# sch_light_rgb.net
KiCad netlist of a schematic drawn in EasyEDA
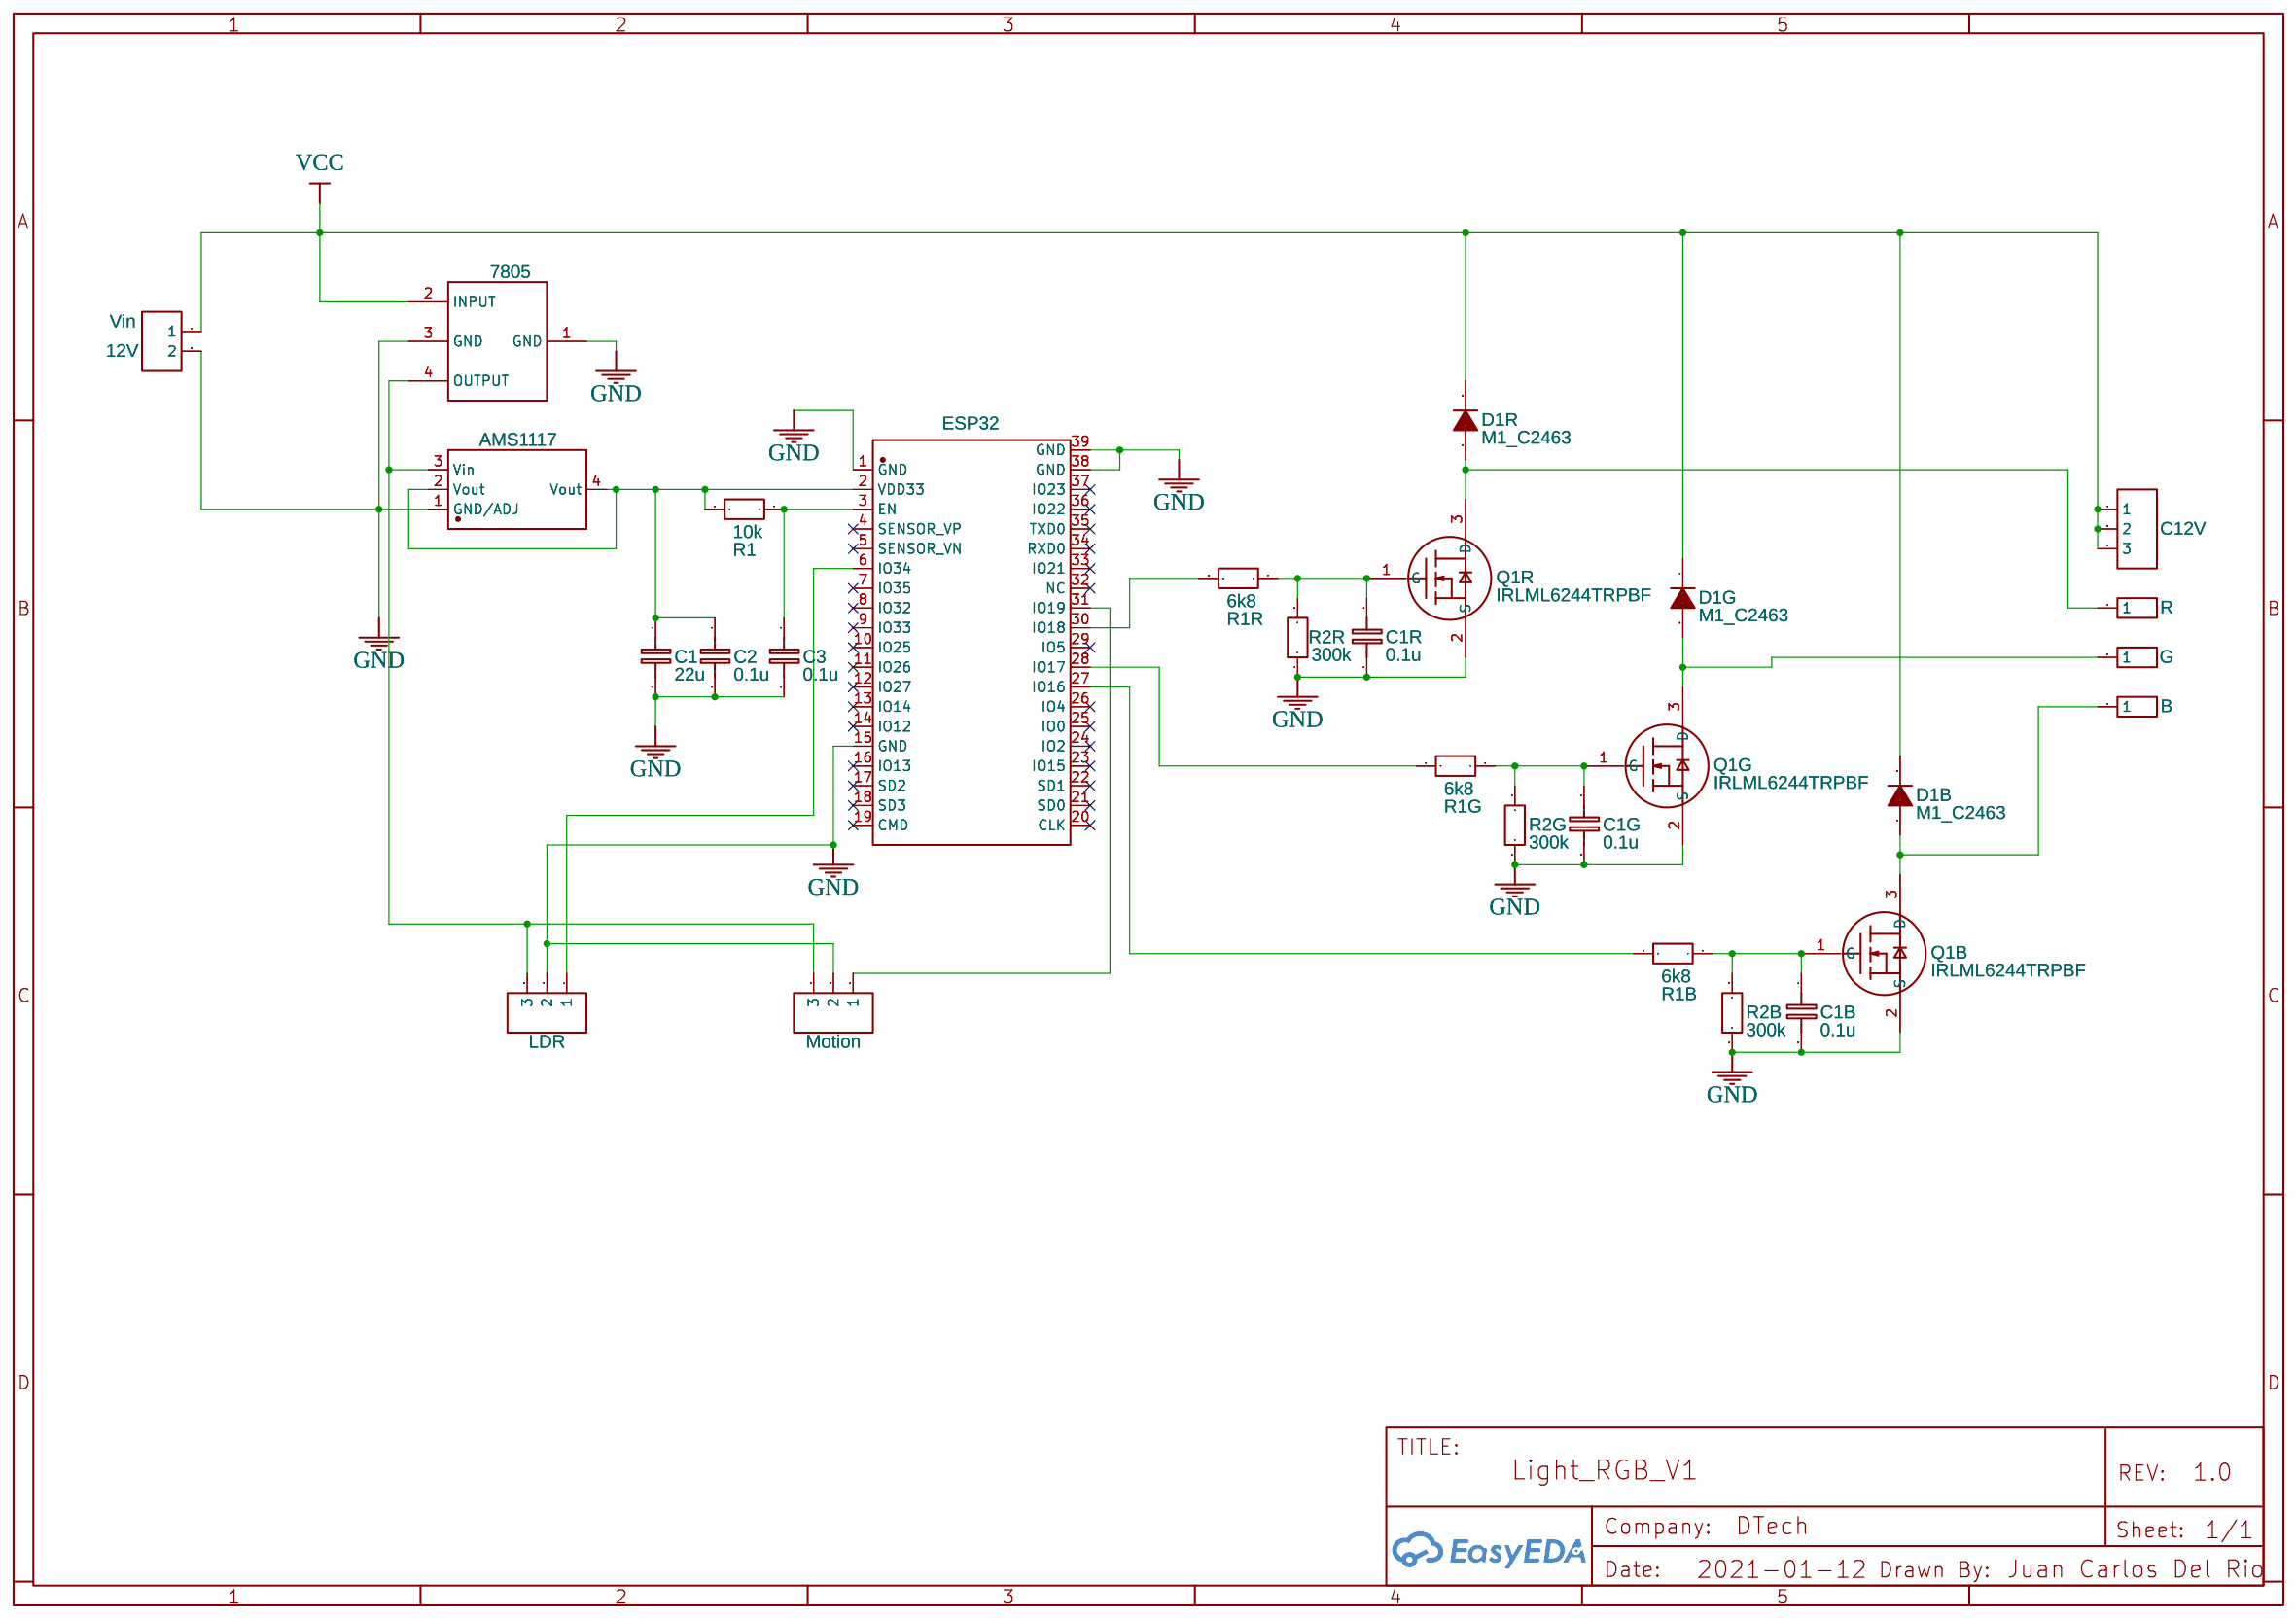
[diagram p0: schematic sheet]

(export (version "E")
  (design (tool "Eeschema 10.0.6"))
  (components
    (comp (ref "12V") (value "Vin") (libsource (lib "") (part "HDR-F-2.54_1x2")))
    (comp (ref "7805") (value "LM7805 SOT223-4") (libsource (lib "") (part "LM7805 SOT223-4")))
    (comp (ref "AMS1117")
      (value "AMS1117-3.3")
      (fields (field (name "Manufacturer") "AMS"))
      (libsource (lib "") (part "AMS1117-3.3"))
    )
    (comp (ref "B") (value "B") (libsource (lib "") (part "HDR-M-2.54_1x1")))
    (comp (ref "C1") (value "22u") (libsource (lib "") (part "C_0805_EU_3")))
    (comp (ref "C1B") (value "0.1u") (libsource (lib "") (part "C_0805_EU_1")))
    (comp (ref "C1G") (value "0.1u") (libsource (lib "") (part "C_0805_EU_2")))
    (comp (ref "C1R") (value "0.1u") (libsource (lib "") (part "C_0805_EU")))
    (comp (ref "C2") (value "0.1u") (libsource (lib "") (part "C_0805_EU_3")))
    (comp (ref "C3") (value "0.1u") (libsource (lib "") (part "C_0805_EU_3")))
    (comp (ref "C12V") (value "C12V") (libsource (lib "") (part "HDR-F-2.54_1x3")))
    (comp (ref "D1B")
      (value "M1_C2463")
      (fields (field (name "Manufacturer Part") "M1") (field (name "Manufacturer") "MDD"))
      (libsource (lib "") (part "M1_C2463"))
    )
    (comp (ref "D1G")
      (value "M1_C2463")
      (fields (field (name "Manufacturer Part") "M1") (field (name "Manufacturer") "MDD"))
      (libsource (lib "") (part "M1_C2463_1"))
    )
    (comp (ref "D1R")
      (value "M1_C2463")
      (fields (field (name "Manufacturer Part") "M1") (field (name "Manufacturer") "MDD"))
      (libsource (lib "") (part "M1_C2463_2"))
    )
    (comp (ref "ESP32")
      (value "ESP32-WROOM-32")
      (fields (field (name "Manufacturer") "Espressif Systems"))
      (libsource (lib "") (part "ESP32-WROOM-32"))
    )
    (comp (ref "G") (value "G") (libsource (lib "") (part "HDR-M-2.54_1x1_1")))
    (comp (ref "LDR") (value "LDR") (libsource (lib "") (part "HDR-F-2.54_1x3_1")))
    (comp (ref "MOTION") (value "Motion") (libsource (lib "") (part "HDR-F-2.54_1x3_2")))
    (comp (ref "Q1B")
      (value "IRLML6244TRPBF")
      (fields (field (name "Manufacturer") "Infineon"))
      (libsource (lib "") (part "IRLML6244TRPBF"))
    )
    (comp (ref "Q1G")
      (value "IRLML6244TRPBF")
      (fields (field (name "Manufacturer") "Infineon"))
      (libsource (lib "") (part "IRLML6244TRPBF_2"))
    )
    (comp (ref "Q1R")
      (value "IRLML6244TRPBF")
      (fields (field (name "Manufacturer") "Infineon"))
      (libsource (lib "") (part "IRLML6244TRPBF_1"))
    )
    (comp (ref "R") (value "R") (libsource (lib "") (part "HDR-M-2.54_1x1_2")))
    (comp (ref "R1") (value "10k") (libsource (lib "") (part "R_1206_EU_5")))
    (comp (ref "R1B") (value "6k8") (libsource (lib "") (part "R_1206_EU_4")))
    (comp (ref "R1G") (value "6k8") (libsource (lib "") (part "R_1206_EU_1")))
    (comp (ref "R1R") (value "6k8") (libsource (lib "") (part "R_1206_EU_2")))
    (comp (ref "R2B") (value "300k") (libsource (lib "") (part "R_1206_EU_6")))
    (comp (ref "R2G") (value "300k") (libsource (lib "") (part "R_1206_EU")))
    (comp (ref "R2R") (value "300k") (libsource (lib "") (part "R_1206_EU_3")))
  )
  (nets
    (net (code "1") (name "GND") (class "Default")
      (node (ref "12V") (pin "2") (pinfunction "2_2") (pintype "input"))
      (node (ref "7805") (pin "1") (pinfunction "GND_1") (pintype "unspecified"))
      (node (ref "7805") (pin "3") (pinfunction "GND_3") (pintype "unspecified"))
      (node (ref "AMS1117") (pin "1") (pinfunction "GND/ADJ_1") (pintype "unspecified"))
      (node (ref "C1") (pin "2") (pinfunction "2_2") (pintype "unspecified"))
      (node (ref "C1B") (pin "2") (pinfunction "2_2") (pintype "unspecified"))
      (node (ref "C1G") (pin "2") (pinfunction "2_2") (pintype "unspecified"))
      (node (ref "C1R") (pin "2") (pinfunction "2_2") (pintype "unspecified"))
      (node (ref "C2") (pin "2") (pinfunction "2_2") (pintype "unspecified"))
      (node (ref "C3") (pin "2") (pinfunction "2_2") (pintype "unspecified"))
      (node (ref "ESP32") (pin "1") (pinfunction "GND_1") (pintype "unspecified"))
      (node (ref "ESP32") (pin "15") (pinfunction "GND_15") (pintype "unspecified"))
      (node (ref "ESP32") (pin "38") (pinfunction "GND_38") (pintype "unspecified"))
      (node (ref "ESP32") (pin "39") (pinfunction "GND_39") (pintype "unspecified"))
      (node (ref "LDR") (pin "2") (pinfunction "2_2") (pintype "input"))
      (node (ref "MOTION") (pin "2") (pinfunction "2_2") (pintype "input"))
      (node (ref "Q1B") (pin "2") (pinfunction "S_2") (pintype "unspecified"))
      (node (ref "Q1G") (pin "2") (pinfunction "S_2") (pintype "unspecified"))
      (node (ref "Q1R") (pin "2") (pinfunction "S_2") (pintype "unspecified"))
      (node (ref "R2B") (pin "1") (pinfunction "1_1") (pintype "unspecified"))
      (node (ref "R2G") (pin "1") (pinfunction "1_1") (pintype "unspecified"))
      (node (ref "R2R") (pin "1") (pinfunction "1_1") (pintype "unspecified"))
    )
    (net (code "2") (name "Net-(7805-OUTPUT)") (class "Default")
      (node (ref "7805") (pin "4") (pinfunction "OUTPUT_4") (pintype "unspecified"))
      (node (ref "AMS1117") (pin "3") (pinfunction "Vin_3") (pintype "unspecified"))
      (node (ref "LDR") (pin "3") (pinfunction "3_3") (pintype "input"))
      (node (ref "MOTION") (pin "3") (pinfunction "3_3") (pintype "input"))
    )
    (net (code "3") (name "Net-(D1B-A)") (class "Default")
      (node (ref "B") (pin "1") (pinfunction "1_1") (pintype "input"))
      (node (ref "D1B") (pin "2") (pinfunction "A_2") (pintype "unspecified"))
      (node (ref "Q1B") (pin "3") (pinfunction "D_3") (pintype "unspecified"))
    )
    (net (code "4") (name "Net-(D1G-A)") (class "Default")
      (node (ref "D1G") (pin "2") (pinfunction "A_2") (pintype "unspecified"))
      (node (ref "G") (pin "1") (pinfunction "1_1") (pintype "input"))
      (node (ref "Q1G") (pin "3") (pinfunction "D_3") (pintype "unspecified"))
    )
    (net (code "5") (name "Net-(D1R-A)") (class "Default")
      (node (ref "D1R") (pin "2") (pinfunction "A_2") (pintype "unspecified"))
      (node (ref "Q1R") (pin "3") (pinfunction "D_3") (pintype "unspecified"))
      (node (ref "R") (pin "1") (pinfunction "1_1") (pintype "input"))
    )
    (net (code "6") (name "Net-(ESP32-EN)") (class "Default")
      (node (ref "C3") (pin "1") (pinfunction "1_1") (pintype "unspecified"))
      (node (ref "ESP32") (pin "3") (pinfunction "EN_3") (pintype "unspecified"))
      (node (ref "R1") (pin "1") (pinfunction "1_1") (pintype "unspecified"))
    )
    (net (code "7") (name "Net-(ESP32-IO16)") (class "Default")
      (node (ref "ESP32") (pin "27") (pinfunction "IO16_27") (pintype "unspecified"))
      (node (ref "R1B") (pin "2") (pinfunction "2_2") (pintype "unspecified"))
    )
    (net (code "8") (name "Net-(ESP32-IO17)") (class "Default")
      (node (ref "ESP32") (pin "28") (pinfunction "IO17_28") (pintype "unspecified"))
      (node (ref "R1G") (pin "2") (pinfunction "2_2") (pintype "unspecified"))
    )
    (net (code "9") (name "Net-(ESP32-IO18)") (class "Default")
      (node (ref "ESP32") (pin "30") (pinfunction "IO18_30") (pintype "unspecified"))
      (node (ref "R1R") (pin "2") (pinfunction "2_2") (pintype "unspecified"))
    )
    (net (code "10") (name "Net-(ESP32-IO19)") (class "Default")
      (node (ref "ESP32") (pin "31") (pinfunction "IO19_31") (pintype "unspecified"))
      (node (ref "MOTION") (pin "1") (pinfunction "1_1") (pintype "input"))
    )
    (net (code "11") (name "Net-(ESP32-IO34)") (class "Default")
      (node (ref "ESP32") (pin "6") (pinfunction "IO34_6") (pintype "unspecified"))
      (node (ref "LDR") (pin "1") (pinfunction "1_1") (pintype "input"))
    )
    (net (code "12") (name "Net-(ESP32-VDD33)") (class "Default")
      (node (ref "AMS1117") (pin "2") (pinfunction "Vout_2") (pintype "unspecified"))
      (node (ref "AMS1117") (pin "4") (pinfunction "Vout_4") (pintype "unspecified"))
      (node (ref "C1") (pin "1") (pinfunction "1_1") (pintype "unspecified"))
      (node (ref "C2") (pin "1") (pinfunction "1_1") (pintype "unspecified"))
      (node (ref "ESP32") (pin "2") (pinfunction "VDD33_2") (pintype "unspecified"))
      (node (ref "R1") (pin "2") (pinfunction "2_2") (pintype "unspecified"))
    )
    (net (code "13") (name "Net-(Q1B-G)") (class "Default")
      (node (ref "C1B") (pin "1") (pinfunction "1_1") (pintype "unspecified"))
      (node (ref "Q1B") (pin "1") (pinfunction "G_1") (pintype "unspecified"))
      (node (ref "R1B") (pin "1") (pinfunction "1_1") (pintype "unspecified"))
      (node (ref "R2B") (pin "2") (pinfunction "2_2") (pintype "unspecified"))
    )
    (net (code "14") (name "Net-(Q1G-G)") (class "Default")
      (node (ref "C1G") (pin "1") (pinfunction "1_1") (pintype "unspecified"))
      (node (ref "Q1G") (pin "1") (pinfunction "G_1") (pintype "unspecified"))
      (node (ref "R1G") (pin "1") (pinfunction "1_1") (pintype "unspecified"))
      (node (ref "R2G") (pin "2") (pinfunction "2_2") (pintype "unspecified"))
    )
    (net (code "15") (name "Net-(Q1R-G)") (class "Default")
      (node (ref "C1R") (pin "1") (pinfunction "1_1") (pintype "unspecified"))
      (node (ref "Q1R") (pin "1") (pinfunction "G_1") (pintype "unspecified"))
      (node (ref "R1R") (pin "1") (pinfunction "1_1") (pintype "unspecified"))
      (node (ref "R2R") (pin "2") (pinfunction "2_2") (pintype "unspecified"))
    )
    (net (code "16") (name "VCC") (class "Default")
      (node (ref "12V") (pin "1") (pinfunction "1_1") (pintype "input"))
      (node (ref "7805") (pin "2") (pinfunction "INPUT_2") (pintype "unspecified"))
      (node (ref "C12V") (pin "1") (pinfunction "1_1") (pintype "input"))
      (node (ref "C12V") (pin "2") (pinfunction "2_2") (pintype "input"))
      (node (ref "C12V") (pin "3") (pinfunction "3_3") (pintype "input"))
      (node (ref "D1B") (pin "1") (pinfunction "K_1") (pintype "unspecified"))
      (node (ref "D1G") (pin "1") (pinfunction "K_1") (pintype "unspecified"))
      (node (ref "D1R") (pin "1") (pinfunction "K_1") (pintype "unspecified"))
    )
    (net (code "17") (name "unconnected-(ESP32-CLK-Pad20)") (class "Default")
      (node (ref "ESP32") (pin "20") (pinfunction "CLK_20") (pintype "unspecified+no_connect"))
    )
    (net (code "18") (name "unconnected-(ESP32-CMD-Pad19)") (class "Default")
      (node (ref "ESP32") (pin "19") (pinfunction "CMD_19") (pintype "unspecified+no_connect"))
    )
    (net (code "19") (name "unconnected-(ESP32-IO0-Pad25)") (class "Default")
      (node (ref "ESP32") (pin "25") (pinfunction "IO0_25") (pintype "unspecified+no_connect"))
    )
    (net (code "20") (name "unconnected-(ESP32-IO2-Pad24)") (class "Default")
      (node (ref "ESP32") (pin "24") (pinfunction "IO2_24") (pintype "unspecified+no_connect"))
    )
    (net (code "21") (name "unconnected-(ESP32-IO4-Pad26)") (class "Default")
      (node (ref "ESP32") (pin "26") (pinfunction "IO4_26") (pintype "unspecified+no_connect"))
    )
    (net (code "22") (name "unconnected-(ESP32-IO5-Pad29)") (class "Default")
      (node (ref "ESP32") (pin "29") (pinfunction "IO5_29") (pintype "unspecified+no_connect"))
    )
    (net (code "23") (name "unconnected-(ESP32-IO12-Pad14)") (class "Default")
      (node (ref "ESP32") (pin "14") (pinfunction "IO12_14") (pintype "unspecified+no_connect"))
    )
    (net (code "24") (name "unconnected-(ESP32-IO13-Pad16)") (class "Default")
      (node (ref "ESP32") (pin "16") (pinfunction "IO13_16") (pintype "unspecified+no_connect"))
    )
    (net (code "25") (name "unconnected-(ESP32-IO14-Pad13)") (class "Default")
      (node (ref "ESP32") (pin "13") (pinfunction "IO14_13") (pintype "unspecified+no_connect"))
    )
    (net (code "26") (name "unconnected-(ESP32-IO15-Pad23)") (class "Default")
      (node (ref "ESP32") (pin "23") (pinfunction "IO15_23") (pintype "unspecified+no_connect"))
    )
    (net (code "27") (name "unconnected-(ESP32-IO21-Pad33)") (class "Default")
      (node (ref "ESP32") (pin "33") (pinfunction "IO21_33") (pintype "unspecified+no_connect"))
    )
    (net (code "28") (name "unconnected-(ESP32-IO22-Pad36)") (class "Default")
      (node (ref "ESP32") (pin "36") (pinfunction "IO22_36") (pintype "unspecified+no_connect"))
    )
    (net (code "29") (name "unconnected-(ESP32-IO23-Pad37)") (class "Default")
      (node (ref "ESP32") (pin "37") (pinfunction "IO23_37") (pintype "unspecified+no_connect"))
    )
    (net (code "30") (name "unconnected-(ESP32-IO25-Pad10)") (class "Default")
      (node (ref "ESP32") (pin "10") (pinfunction "IO25_10") (pintype "unspecified+no_connect"))
    )
    (net (code "31") (name "unconnected-(ESP32-IO26-Pad11)") (class "Default")
      (node (ref "ESP32") (pin "11") (pinfunction "IO26_11") (pintype "unspecified+no_connect"))
    )
    (net (code "32") (name "unconnected-(ESP32-IO27-Pad12)") (class "Default")
      (node (ref "ESP32") (pin "12") (pinfunction "IO27_12") (pintype "unspecified+no_connect"))
    )
    (net (code "33") (name "unconnected-(ESP32-IO32-Pad8)") (class "Default")
      (node (ref "ESP32") (pin "8") (pinfunction "IO32_8") (pintype "unspecified+no_connect"))
    )
    (net (code "34") (name "unconnected-(ESP32-IO33-Pad9)") (class "Default")
      (node (ref "ESP32") (pin "9") (pinfunction "IO33_9") (pintype "unspecified+no_connect"))
    )
    (net (code "35") (name "unconnected-(ESP32-IO35-Pad7)") (class "Default")
      (node (ref "ESP32") (pin "7") (pinfunction "IO35_7") (pintype "unspecified+no_connect"))
    )
    (net (code "36") (name "unconnected-(ESP32-NC-Pad32)") (class "Default")
      (node (ref "ESP32") (pin "32") (pinfunction "NC_32") (pintype "unspecified+no_connect"))
    )
    (net (code "37") (name "unconnected-(ESP32-RXD0-Pad34)") (class "Default")
      (node (ref "ESP32") (pin "34") (pinfunction "RXD0_34") (pintype "unspecified+no_connect"))
    )
    (net (code "38") (name "unconnected-(ESP32-SD0-Pad21)") (class "Default")
      (node (ref "ESP32") (pin "21") (pinfunction "SD0_21") (pintype "unspecified+no_connect"))
    )
    (net (code "39") (name "unconnected-(ESP32-SD1-Pad22)") (class "Default")
      (node (ref "ESP32") (pin "22") (pinfunction "SD1_22") (pintype "unspecified+no_connect"))
    )
    (net (code "40") (name "unconnected-(ESP32-SD2-Pad17)") (class "Default")
      (node (ref "ESP32") (pin "17") (pinfunction "SD2_17") (pintype "unspecified+no_connect"))
    )
    (net (code "41") (name "unconnected-(ESP32-SD3-Pad18)") (class "Default")
      (node (ref "ESP32") (pin "18") (pinfunction "SD3_18") (pintype "unspecified+no_connect"))
    )
    (net (code "42") (name "unconnected-(ESP32-SENSOR_VN-Pad5)") (class "Default")
      (node (ref "ESP32") (pin "5") (pinfunction "SENSOR_VN_5") (pintype "unspecified+no_connect"))
    )
    (net (code "43") (name "unconnected-(ESP32-SENSOR_VP-Pad4)") (class "Default")
      (node (ref "ESP32") (pin "4") (pinfunction "SENSOR_VP_4") (pintype "unspecified+no_connect"))
    )
    (net (code "44") (name "unconnected-(ESP32-TXD0-Pad35)") (class "Default")
      (node (ref "ESP32") (pin "35") (pinfunction "TXD0_35") (pintype "unspecified+no_connect"))
    )
  )
)
